# Prototype3.net
KiCad netlist of a schematic drawn in EAGLE
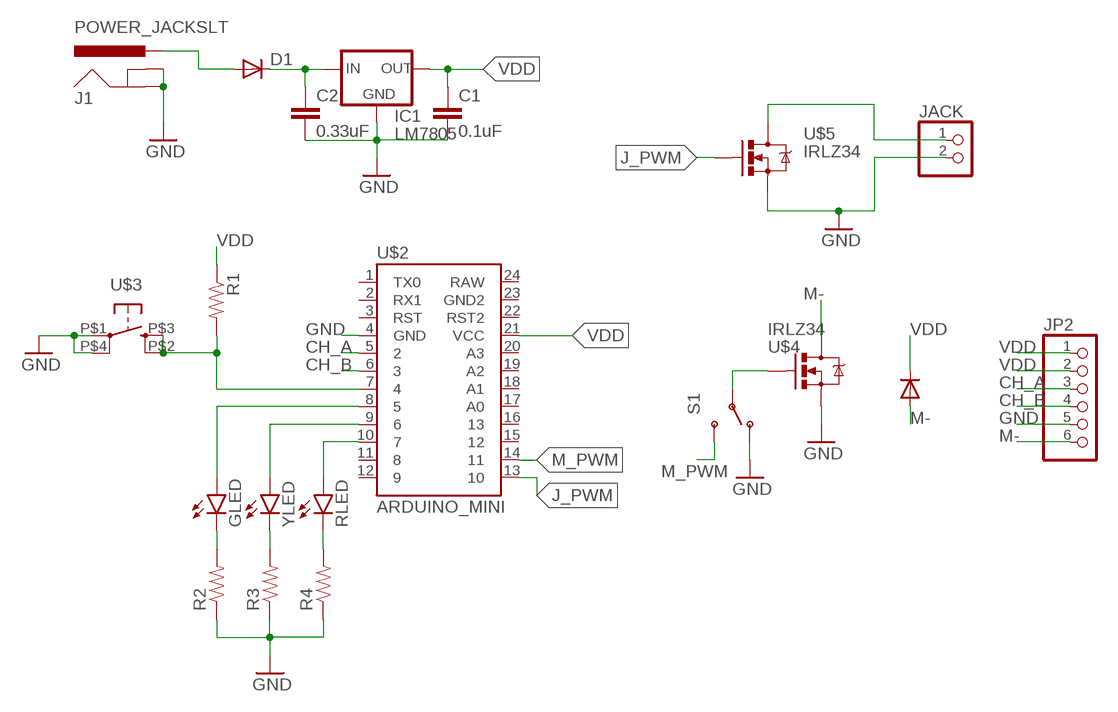
[diagram p0: schematic, sheet 1]

(export (version "E")
  (design (tool "Eeschema 10.0.6"))
  (components
    (comp (ref "C1")
      (value "0.1uF")
      (footprint "eagle-import:C5B2.5")
      (libsource (lib "eagle-import") (part "C5/2.5"))
    )
    (comp (ref "C2")
      (value "0.33uF")
      (footprint "eagle-import:C5B2.5")
      (libsource (lib "eagle-import") (part "C5/2.5"))
    )
    (comp (ref "D1")
      (value "SCHOTTKY-DIODE")
      (footprint "eagle-import:SMD-DIODE")
      (libsource (lib "eagle-import") (part "SCHOTTKY-DIODE"))
    )
    (comp (ref "GLED")
      (value "LED3MM")
      (footprint "eagle-import:LED3MM")
      (libsource (lib "eagle-import") (part "LED3MM"))
    )
    (comp (ref "IC1")
      (value "LM7805")
      (footprint "eagle-import:TO-220(2)")
      (libsource (lib "eagle-import") (part "LM7805"))
    )
    (comp (ref "J1")
      (value "POWER_JACKSLT")
      (footprint "eagle-import:POWER_JACK_SLOT")
      (libsource (lib "eagle-import") (part "POWER_JACKSLT"))
    )
    (comp (ref "JACK")
      (value "PINHD-1X2")
      (footprint "eagle-import:1X02")
      (libsource (lib "eagle-import") (part "PINHD-1X2"))
    )
    (comp (ref "JP2")
      (value "PINHD-1X6")
      (footprint "eagle-import:1X06")
      (libsource (lib "eagle-import") (part "PINHD-1X6"))
    )
    (comp (ref "R1")
      (value "RESISTORAXIAL-0.3")
      (footprint "eagle-import:AXIAL-0.3")
      (libsource (lib "eagle-import") (part "RESISTORAXIAL-0.3"))
    )
    (comp (ref "R2")
      (value "RESISTORAXIAL-0.3")
      (footprint "eagle-import:AXIAL-0.3")
      (libsource (lib "eagle-import") (part "RESISTORAXIAL-0.3"))
    )
    (comp (ref "R3")
      (value "RESISTORAXIAL-0.3")
      (footprint "eagle-import:AXIAL-0.3")
      (libsource (lib "eagle-import") (part "RESISTORAXIAL-0.3"))
    )
    (comp (ref "R4")
      (value "RESISTORAXIAL-0.3")
      (footprint "eagle-import:AXIAL-0.3")
      (libsource (lib "eagle-import") (part "RESISTORAXIAL-0.3"))
    )
    (comp (ref "RLED")
      (value "LED3MM")
      (footprint "eagle-import:LED3MM")
      (libsource (lib "eagle-import") (part "LED3MM"))
    )
    (comp (ref "S1")
      (value "SWITCH-SPDTKIT")
      (footprint "eagle-import:SWITCH-SPDT_KIT")
      (libsource (lib "eagle-import") (part "SWITCH-SPDTKIT"))
    )
    (comp (ref "U$1")
      (value "SCHOTTKY-DIODE")
      (footprint "eagle-import:SMD-DIODE")
      (libsource (lib "eagle-import") (part "SCHOTTKY-DIODE"))
    )
    (comp (ref "U$2")
      (value "ARDUINO_MINI")
      (footprint "eagle-import:ARDUINO_MINI")
      (libsource (lib "eagle-import") (part "ARDUINO_MINI"))
    )
    (comp (ref "U$3")
      (value "PUSH-BUTTON")
      (footprint "eagle-import:PUSHBTTN")
      (libsource (lib "eagle-import") (part "PUSH-BUTTON"))
    )
    (comp (ref "U$4")
      (value "IRLZ34")
      (footprint "eagle-import:TO-220(2)")
      (libsource (lib "eagle-import") (part "IRLZ34"))
    )
    (comp (ref "U$5")
      (value "IRLZ34")
      (footprint "eagle-import:TO-220(2)")
      (libsource (lib "eagle-import") (part "IRLZ34"))
    )
    (comp (ref "YLED")
      (value "LED3MM")
      (footprint "eagle-import:LED3MM")
      (libsource (lib "eagle-import") (part "LED3MM"))
    )
  )
  (nets
    (net (code "1") (name "/CH_A") (class "Default")
      (node (ref "JP2") (pin "3") (pinfunction "3_3") (pintype "passive"))
      (node (ref "U$2") (pin "5") (pinfunction "2_5") (pintype "bidirectional"))
    )
    (net (code "2") (name "/CH_B") (class "Default")
      (node (ref "JP2") (pin "4") (pinfunction "4_4") (pintype "passive"))
      (node (ref "U$2") (pin "6") (pinfunction "3_6") (pintype "bidirectional"))
    )
    (net (code "3") (name "/M-") (class "Default")
      (node (ref "JP2") (pin "6") (pinfunction "6_6") (pintype "passive"))
      (node (ref "U$1") (pin "P$1") (pinfunction "A_P$1") (pintype "passive"))
      (node (ref "U$4") (pin "GND") (pinfunction "D_GND") (pintype "passive"))
    )
    (net (code "4") (name "GND") (class "Default")
      (node (ref "C1") (pin "2") (pinfunction "2_2") (pintype "passive"))
      (node (ref "C2") (pin "2") (pinfunction "2_2") (pintype "passive"))
      (node (ref "IC1") (pin "GND") (pinfunction "GND_GND") (pintype "input"))
      (node (ref "J1") (pin "GND@1") (pinfunction "GNDBREAK_GND@1") (pintype "bidirectional"))
      (node (ref "J1") (pin "GND@2") (pinfunction "GND_GND@2") (pintype "bidirectional"))
      (node (ref "JACK") (pin "2") (pinfunction "2_2") (pintype "passive"))
      (node (ref "JP2") (pin "5") (pinfunction "5_5") (pintype "passive"))
      (node (ref "R2") (pin "P$1") (pinfunction "1_P$1") (pintype "passive"))
      (node (ref "R3") (pin "P$1") (pinfunction "1_P$1") (pintype "passive"))
      (node (ref "R4") (pin "P$1") (pinfunction "1_P$1") (pintype "passive"))
      (node (ref "S1") (pin "1") (pinfunction "O_1") (pintype "passive"))
      (node (ref "U$2") (pin "4") (pinfunction "GND_4") (pintype "bidirectional"))
      (node (ref "U$3") (pin "P$1") (pinfunction "1_P$1") (pintype "passive"))
      (node (ref "U$3") (pin "P$4") (pinfunction "2_P$4") (pintype "passive"))
      (node (ref "U$4") (pin "OUT") (pinfunction "S_OUT") (pintype "passive"))
      (node (ref "U$5") (pin "OUT") (pinfunction "S_OUT") (pintype "passive"))
    )
    (net (code "5") (name "J_PWM") (class "Default")
      (node (ref "U$2") (pin "13") (pinfunction "10_13") (pintype "bidirectional"))
      (node (ref "U$5") (pin "IN") (pinfunction "G_IN") (pintype "passive"))
    )
    (net (code "6") (name "M_PWM") (class "Default")
      (node (ref "S1") (pin "3") (pinfunction "S_3") (pintype "passive"))
      (node (ref "U$2") (pin "14") (pinfunction "11_14") (pintype "bidirectional"))
    )
    (net (code "7") (name "Net-(D1-A)") (class "Default")
      (node (ref "D1") (pin "P$1") (pinfunction "A_P$1") (pintype "passive"))
      (node (ref "J1") (pin "PWR") (pinfunction "PWR_PWR") (pintype "bidirectional"))
    )
    (net (code "8") (name "Net-(D1-C)") (class "Default")
      (node (ref "C2") (pin "1") (pinfunction "1_1") (pintype "passive"))
      (node (ref "D1") (pin "P$2") (pinfunction "C_P$2") (pintype "passive"))
      (node (ref "IC1") (pin "IN") (pinfunction "IN_IN") (pintype "input"))
    )
    (net (code "9") (name "Net-(GLED-C)") (class "Default")
      (node (ref "GLED") (pin "K") (pinfunction "C_K") (pintype "passive"))
      (node (ref "R2") (pin "P$2") (pinfunction "2_P$2") (pintype "passive"))
    )
    (net (code "10") (name "Net-(R1-2)") (class "Default")
      (node (ref "R1") (pin "P$2") (pinfunction "2_P$2") (pintype "passive"))
      (node (ref "U$2") (pin "7") (pinfunction "4_7") (pintype "bidirectional"))
      (node (ref "U$3") (pin "P$2") (pinfunction "4_P$2") (pintype "passive"))
      (node (ref "U$3") (pin "P$3") (pinfunction "3_P$3") (pintype "passive"))
    )
    (net (code "11") (name "Net-(R3-2)") (class "Default")
      (node (ref "R3") (pin "P$2") (pinfunction "2_P$2") (pintype "passive"))
      (node (ref "YLED") (pin "K") (pinfunction "C_K") (pintype "passive"))
    )
    (net (code "12") (name "Net-(R4-2)") (class "Default")
      (node (ref "R4") (pin "P$2") (pinfunction "2_P$2") (pintype "passive"))
      (node (ref "RLED") (pin "K") (pinfunction "C_K") (pintype "passive"))
    )
    (net (code "13") (name "Net-(S1-P)") (class "Default")
      (node (ref "S1") (pin "2") (pinfunction "P_2") (pintype "passive"))
      (node (ref "U$4") (pin "IN") (pinfunction "G_IN") (pintype "passive"))
    )
    (net (code "14") (name "Net-(U$2-5)") (class "Default")
      (node (ref "GLED") (pin "A") (pinfunction "A_A") (pintype "passive"))
      (node (ref "U$2") (pin "8") (pinfunction "5_8") (pintype "bidirectional"))
    )
    (net (code "15") (name "Net-(U$2-6)") (class "Default")
      (node (ref "U$2") (pin "9") (pinfunction "6_9") (pintype "bidirectional"))
      (node (ref "YLED") (pin "A") (pinfunction "A_A") (pintype "passive"))
    )
    (net (code "16") (name "Net-(U$2-7)") (class "Default")
      (node (ref "RLED") (pin "A") (pinfunction "A_A") (pintype "passive"))
      (node (ref "U$2") (pin "10") (pinfunction "7_10") (pintype "bidirectional"))
    )
    (net (code "17") (name "Net-(U$5-D)") (class "Default")
      (node (ref "JACK") (pin "1") (pinfunction "1_1") (pintype "passive"))
      (node (ref "U$5") (pin "GND") (pinfunction "D_GND") (pintype "passive"))
    )
    (net (code "18") (name "VDD") (class "Default")
      (node (ref "C1") (pin "1") (pinfunction "1_1") (pintype "passive"))
      (node (ref "IC1") (pin "OUT") (pinfunction "OUT_OUT") (pintype "output"))
      (node (ref "JP2") (pin "1") (pinfunction "1_1") (pintype "passive"))
      (node (ref "JP2") (pin "2") (pinfunction "2_2") (pintype "passive"))
      (node (ref "R1") (pin "P$1") (pinfunction "1_P$1") (pintype "passive"))
      (node (ref "U$1") (pin "P$2") (pinfunction "C_P$2") (pintype "passive"))
      (node (ref "U$2") (pin "21") (pinfunction "VCC_21") (pintype "bidirectional"))
    )
    (net (code "19") (name "unconnected-(U$2-8-Pad11)") (class "Default")
      (node (ref "U$2") (pin "11") (pinfunction "8_11") (pintype "bidirectional"))
    )
    (net (code "20") (name "unconnected-(U$2-9-Pad12)") (class "Default")
      (node (ref "U$2") (pin "12") (pinfunction "9_12") (pintype "bidirectional"))
    )
    (net (code "21") (name "unconnected-(U$2-12-Pad15)") (class "Default")
      (node (ref "U$2") (pin "15") (pinfunction "12_15") (pintype "bidirectional"))
    )
    (net (code "22") (name "unconnected-(U$2-13-Pad16)") (class "Default")
      (node (ref "U$2") (pin "16") (pinfunction "13_16") (pintype "bidirectional"))
    )
    (net (code "23") (name "unconnected-(U$2-A0-Pad17)") (class "Default")
      (node (ref "U$2") (pin "17") (pinfunction "A0_17") (pintype "bidirectional"))
    )
    (net (code "24") (name "unconnected-(U$2-A1-Pad18)") (class "Default")
      (node (ref "U$2") (pin "18") (pinfunction "A1_18") (pintype "bidirectional"))
    )
    (net (code "25") (name "unconnected-(U$2-A2-Pad19)") (class "Default")
      (node (ref "U$2") (pin "19") (pinfunction "A2_19") (pintype "bidirectional"))
    )
    (net (code "26") (name "unconnected-(U$2-A3-Pad20)") (class "Default")
      (node (ref "U$2") (pin "20") (pinfunction "A3_20") (pintype "bidirectional"))
    )
    (net (code "27") (name "unconnected-(U$2-GND2-Pad23)") (class "Default")
      (node (ref "U$2") (pin "23") (pinfunction "GND2_23") (pintype "bidirectional"))
    )
    (net (code "28") (name "unconnected-(U$2-RAW-Pad24)") (class "Default")
      (node (ref "U$2") (pin "24") (pinfunction "RAW_24") (pintype "bidirectional"))
    )
    (net (code "29") (name "unconnected-(U$2-RST-Pad3)") (class "Default")
      (node (ref "U$2") (pin "3") (pinfunction "RST_3") (pintype "bidirectional"))
    )
    (net (code "30") (name "unconnected-(U$2-RST2-Pad22)") (class "Default")
      (node (ref "U$2") (pin "22") (pinfunction "RST2_22") (pintype "bidirectional"))
    )
    (net (code "31") (name "unconnected-(U$2-RX1-Pad2)") (class "Default")
      (node (ref "U$2") (pin "2") (pinfunction "RX1_2") (pintype "bidirectional"))
    )
    (net (code "32") (name "unconnected-(U$2-TX0-Pad1)") (class "Default")
      (node (ref "U$2") (pin "1") (pinfunction "TX0_1") (pintype "bidirectional"))
    )
  )
)
